# ai.net
KiCad netlist of a schematic drawn in Altium Designer
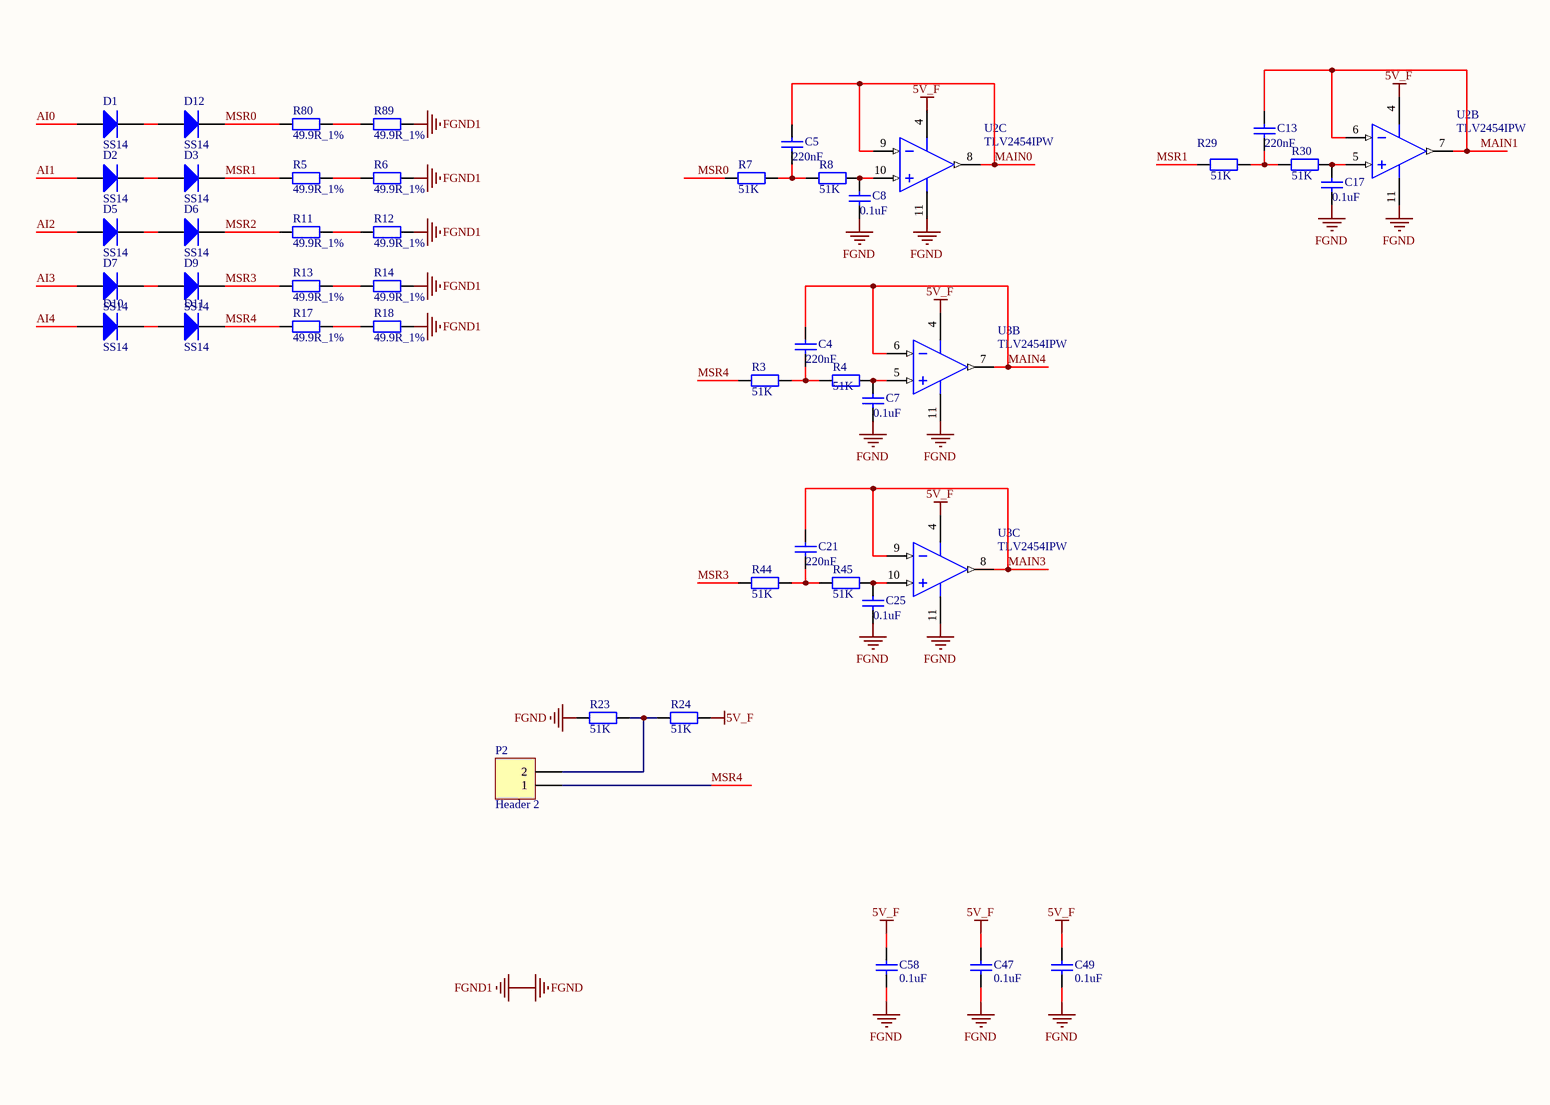
[diagram p0: ai.SchDoc, top left]
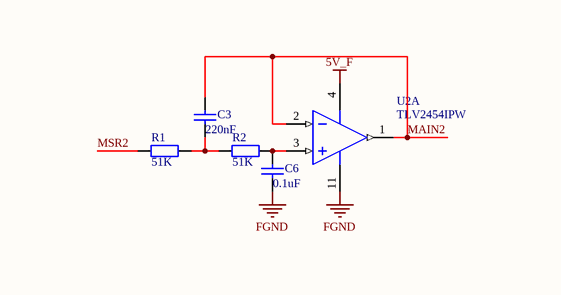
[diagram p1: ai.SchDoc, top right]
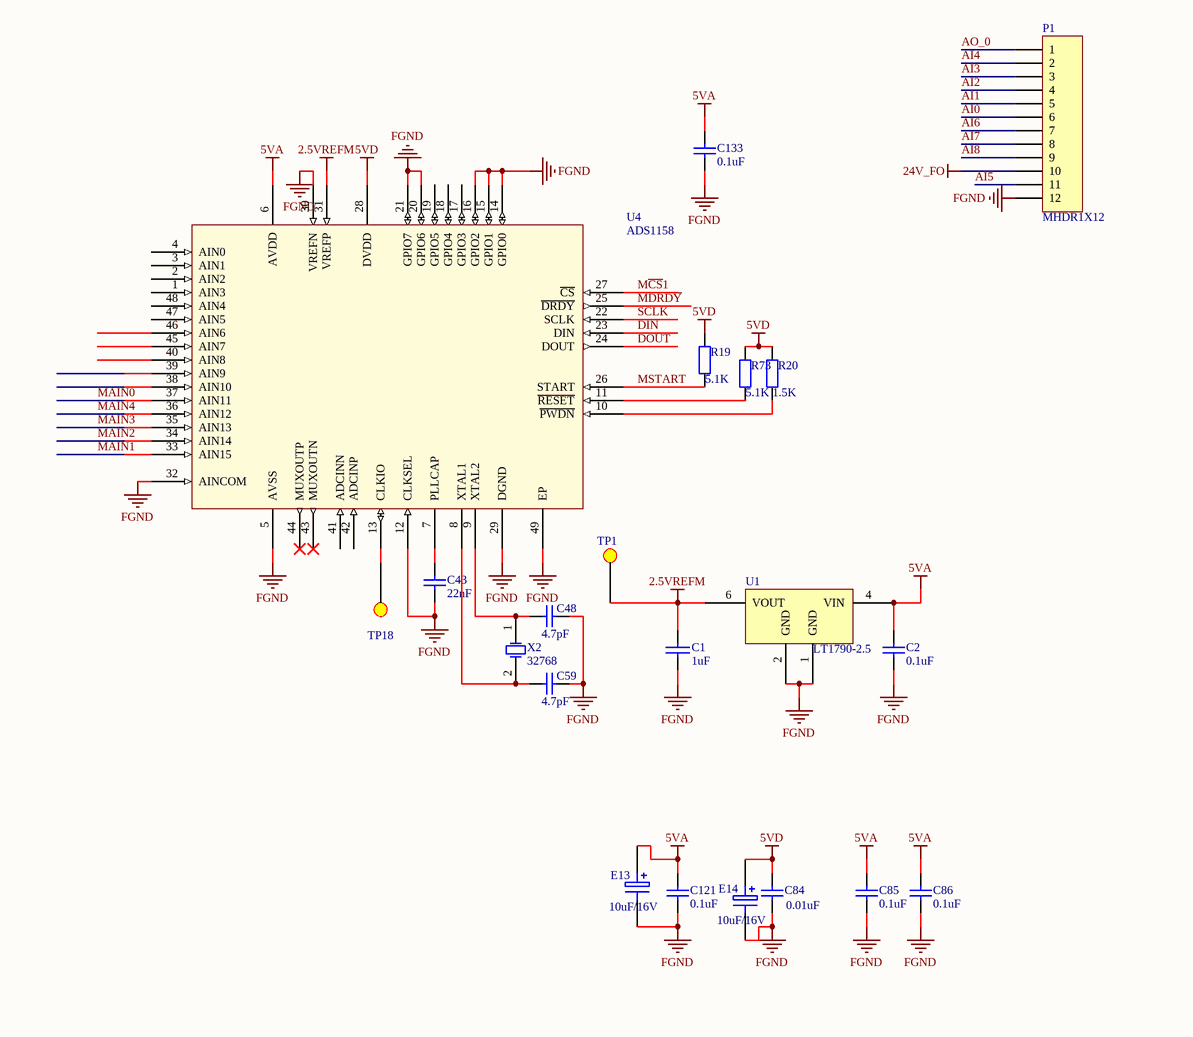
[diagram p2: ai.SchDoc, bottom left]
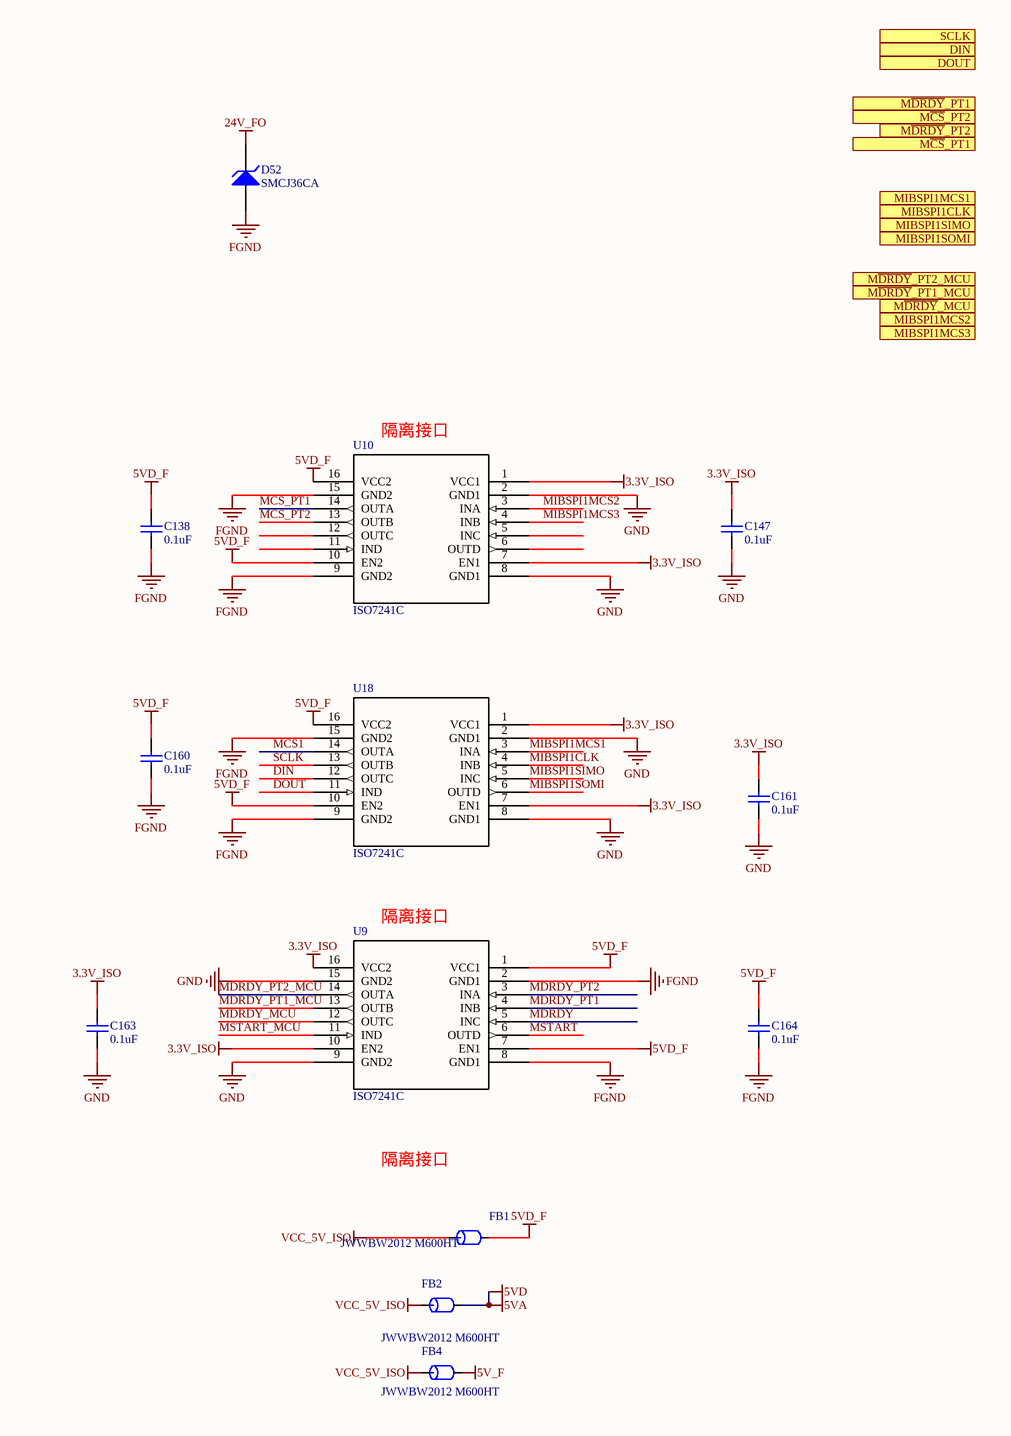
[diagram p3: ai.SchDoc, bottom right]

(export (version "E")
  (design (tool "Eeschema 10.0.6"))
  (components
    (comp (ref "C1")
      (value "1uF")
      (footprint "0603C")
      (description "Capacitor")
      (libsource (lib "*") (part "CAP"))
    )
    (comp (ref "C2")
      (value "0.1uF")
      (footprint "0603C")
      (description "Capacitor")
      (fields (field (name "PUBLISHER") "Altium Limited"))
      (libsource (lib "Miscellaneous Devices") (part "Cap"))
    )
    (comp (ref "C3")
      (value "220nF")
      (footprint "0805C")
      (description "Capacitor")
      (fields (field (name "PUBLISHER") "Altium Limited"))
      (libsource (lib "Miscellaneous Devices") (part "Cap"))
    )
    (comp (ref "C4")
      (value "220nF")
      (footprint "0805C")
      (description "Capacitor")
      (fields (field (name "PUBLISHER") "Altium Limited"))
      (libsource (lib "Miscellaneous Devices") (part "Cap"))
    )
    (comp (ref "C5")
      (value "220nF")
      (footprint "0805C")
      (description "Capacitor")
      (fields (field (name "PUBLISHER") "Altium Limited"))
      (libsource (lib "Miscellaneous Devices") (part "Cap"))
    )
    (comp (ref "C6")
      (value "0.1uF")
      (footprint "0603C")
      (description "Capacitor")
      (fields (field (name "PUBLISHER") "Altium Limited"))
      (libsource (lib "Miscellaneous Devices") (part "Cap"))
    )
    (comp (ref "C7")
      (value "0.1uF")
      (footprint "0603C")
      (description "Capacitor")
      (fields (field (name "PUBLISHER") "Altium Limited"))
      (libsource (lib "Miscellaneous Devices") (part "Cap"))
    )
    (comp (ref "C8")
      (value "0.1uF")
      (footprint "0603C")
      (description "Capacitor")
      (fields (field (name "PUBLISHER") "Altium Limited"))
      (libsource (lib "Miscellaneous Devices") (part "Cap"))
    )
    (comp (ref "C13")
      (value "220nF")
      (footprint "0805C")
      (description "Capacitor")
      (fields (field (name "PUBLISHER") "Altium Limited"))
      (libsource (lib "Miscellaneous Devices") (part "Cap"))
    )
    (comp (ref "C17")
      (value "0.1uF")
      (footprint "0603C")
      (description "Capacitor")
      (fields (field (name "PUBLISHER") "Altium Limited"))
      (libsource (lib "Miscellaneous Devices") (part "Cap"))
    )
    (comp (ref "C21")
      (value "220nF")
      (footprint "0805C")
      (description "Capacitor")
      (fields (field (name "PUBLISHER") "Altium Limited"))
      (libsource (lib "Miscellaneous Devices") (part "Cap"))
    )
    (comp (ref "C25")
      (value "0.1uF")
      (footprint "0603C")
      (description "Capacitor")
      (fields (field (name "PUBLISHER") "Altium Limited"))
      (libsource (lib "Miscellaneous Devices") (part "Cap"))
    )
    (comp (ref "C43")
      (value "22nF")
      (footprint "0805C")
      (description "Capacitor")
      (fields (field (name "PUBLISHER") "Altium Limited"))
      (libsource (lib "Miscellaneous Devices") (part "Cap"))
    )
    (comp (ref "C47")
      (value "0.1uF")
      (footprint "0603C")
      (description "Capacitor")
      (fields (field (name "PUBLISHER") "Altium Limited"))
      (libsource (lib "Miscellaneous Devices") (part "Cap"))
    )
    (comp (ref "C48")
      (value "4.7pF")
      (footprint "0603C")
      (description "Capacitor")
      (fields (field (name "PUBLISHER") "Altium Limited"))
      (libsource (lib "Miscellaneous Devices") (part "Cap"))
    )
    (comp (ref "C49")
      (value "0.1uF")
      (footprint "0603C")
      (description "Capacitor")
      (fields (field (name "PUBLISHER") "Altium Limited"))
      (libsource (lib "Miscellaneous Devices") (part "Cap"))
    )
    (comp (ref "C58")
      (value "0.1uF")
      (footprint "0603C")
      (description "Capacitor")
      (fields (field (name "PUBLISHER") "Altium Limited"))
      (libsource (lib "Miscellaneous Devices") (part "Cap"))
    )
    (comp (ref "C59")
      (value "4.7pF")
      (footprint "0603C")
      (description "Capacitor")
      (fields (field (name "PUBLISHER") "Altium Limited"))
      (libsource (lib "Miscellaneous Devices") (part "Cap"))
    )
    (comp (ref "C84")
      (value "0.01uF")
      (footprint "0603C")
      (description "Capacitor")
      (fields (field (name "PUBLISHER") "Altium Limited"))
      (libsource (lib "Miscellaneous Devices") (part "Cap"))
    )
    (comp (ref "C85")
      (value "0.1uF")
      (footprint "0603C")
      (description "Capacitor")
      (fields (field (name "PUBLISHER") "Altium Limited"))
      (libsource (lib "Miscellaneous Devices") (part "Cap"))
    )
    (comp (ref "C86")
      (value "0.1uF")
      (footprint "0603C")
      (description "Capacitor")
      (fields (field (name "PUBLISHER") "Altium Limited"))
      (libsource (lib "Miscellaneous Devices") (part "Cap"))
    )
    (comp (ref "C121")
      (value "0.1uF")
      (footprint "0603C")
      (description "Capacitor")
      (fields (field (name "PUBLISHER") "Altium Limited"))
      (libsource (lib "Miscellaneous Devices") (part "Cap"))
    )
    (comp (ref "C133")
      (value "0.1uF")
      (footprint "0603C")
      (description "Capacitor")
      (fields (field (name "PUBLISHER") "Altium Limited"))
      (libsource (lib "Miscellaneous Devices") (part "Cap"))
    )
    (comp (ref "C138")
      (value "0.1uF")
      (footprint "0603C")
      (description "Capacitor")
      (fields (field (name "PUBLISHER") "Altium Limited"))
      (libsource (lib "Miscellaneous Devices") (part "Cap"))
    )
    (comp (ref "C147")
      (value "0.1uF")
      (footprint "0603C")
      (description "Capacitor")
      (fields (field (name "PUBLISHER") "Altium Limited"))
      (libsource (lib "Miscellaneous Devices") (part "Cap"))
    )
    (comp (ref "C160")
      (value "0.1uF")
      (footprint "0603C")
      (description "Capacitor")
      (fields (field (name "PUBLISHER") "Altium Limited"))
      (libsource (lib "Miscellaneous Devices") (part "Cap"))
    )
    (comp (ref "C161")
      (value "0.1uF")
      (footprint "0603C")
      (description "Capacitor")
      (fields (field (name "PUBLISHER") "Altium Limited"))
      (libsource (lib "Miscellaneous Devices") (part "Cap"))
    )
    (comp (ref "C163")
      (value "0.1uF")
      (footprint "0603C")
      (description "Capacitor")
      (fields (field (name "PUBLISHER") "Altium Limited"))
      (libsource (lib "Miscellaneous Devices") (part "Cap"))
    )
    (comp (ref "C164")
      (value "0.1uF")
      (footprint "0603C")
      (description "Capacitor")
      (fields (field (name "PUBLISHER") "Altium Limited"))
      (libsource (lib "Miscellaneous Devices") (part "Cap"))
    )
    (comp (ref "D1")
      (value "SS14")
      (footprint "DO-214AC")
      (description "Default Diode")
      (fields (field (name "PUBLISHER") "Altium Limited"))
      (libsource (lib "Miscellaneous Devices") (part "Diode"))
    )
    (comp (ref "D2")
      (value "SS14")
      (footprint "DO-214AC")
      (description "Default Diode")
      (fields (field (name "PUBLISHER") "Altium Limited"))
      (libsource (lib "Miscellaneous Devices") (part "Diode"))
    )
    (comp (ref "D3")
      (value "SS14")
      (footprint "DO-214AC")
      (description "Default Diode")
      (fields (field (name "PUBLISHER") "Altium Limited"))
      (libsource (lib "Miscellaneous Devices") (part "Diode"))
    )
    (comp (ref "D5")
      (value "SS14")
      (footprint "DO-214AC")
      (description "Default Diode")
      (fields (field (name "PUBLISHER") "Altium Limited"))
      (libsource (lib "Miscellaneous Devices") (part "Diode"))
    )
    (comp (ref "D6")
      (value "SS14")
      (footprint "DO-214AC")
      (description "Default Diode")
      (fields (field (name "PUBLISHER") "Altium Limited"))
      (libsource (lib "Miscellaneous Devices") (part "Diode"))
    )
    (comp (ref "D7")
      (value "SS14")
      (footprint "DO-214AC")
      (description "Default Diode")
      (fields (field (name "PUBLISHER") "Altium Limited"))
      (libsource (lib "Miscellaneous Devices") (part "Diode"))
    )
    (comp (ref "D9")
      (value "SS14")
      (footprint "DO-214AC")
      (description "Default Diode")
      (fields (field (name "PUBLISHER") "Altium Limited"))
      (libsource (lib "Miscellaneous Devices") (part "Diode"))
    )
    (comp (ref "D10")
      (value "SS14")
      (footprint "DO-214AC")
      (description "Default Diode")
      (fields (field (name "PUBLISHER") "Altium Limited"))
      (libsource (lib "Miscellaneous Devices") (part "Diode"))
    )
    (comp (ref "D11")
      (value "SS14")
      (footprint "DO-214AC")
      (description "Default Diode")
      (fields (field (name "PUBLISHER") "Altium Limited"))
      (libsource (lib "Miscellaneous Devices") (part "Diode"))
    )
    (comp (ref "D12")
      (value "SS14")
      (footprint "DO-214AC")
      (description "Default Diode")
      (fields (field (name "PUBLISHER") "Altium Limited"))
      (libsource (lib "Miscellaneous Devices") (part "Diode"))
    )
    (comp (ref "D52")
      (value "SMCJ36CA")
      (footprint "SMC")
      (description "SMBJ36CA")
      (fields (field (name "PUBLISHER") "Altium Limited"))
      (libsource (lib "Miscellaneous Devices") (part "D Zener"))
    )
    (comp (ref "E13")
      (value "10uF/16V")
      (footprint "C3528")
      (description "Electrolytic Capacitor")
      (libsource (lib "*") (part "ELECTRO1"))
    )
    (comp (ref "E14")
      (value "10uF/16V")
      (footprint "C3528")
      (description "Electrolytic Capacitor")
      (libsource (lib "*") (part "ELECTRO1"))
    )
    (comp (ref "FB1")
      (value "JWWBW2012 M600HT")
      (footprint "0805R")
      (libsource (lib "Schlib_20110825") (part "FB"))
    )
    (comp (ref "FB2")
      (value "JWWBW2012 M600HT")
      (footprint "0805R")
      (libsource (lib "Schlib_20110825") (part "FB"))
    )
    (comp (ref "FB4")
      (value "JWWBW2012 M600HT")
      (footprint "0805R")
      (libsource (lib "Schlib_20110825") (part "FB"))
    )
    (comp (ref "P1")
      (value "MHDR1X12")
      (footprint "2ETYR-5.08-12P-14-100")
      (description "Header, 12-Pin")
      (fields (field (name "PUBLISHER") "Altium Limited"))
      (libsource (lib "Miscellaneous Connectors") (part "MHDR1X12"))
    )
    (comp (ref "P2")
      (value "Header 2")
      (footprint "HDR1X2")
      (description "Header, 2-Pin")
      (fields (field (name "PUBLISHER") "Altium Limited"))
      (libsource (lib "Miscellaneous Connectors") (part "Header 2"))
    )
    (comp (ref "R1") (value "51K") (footprint "0603R") (libsource (lib "MQlibrary") (part "Res0805M")))
    (comp (ref "R2") (value "51K") (footprint "0603R") (libsource (lib "MQlibrary") (part "Res0805M")))
    (comp (ref "R3") (value "51K") (footprint "0603R") (libsource (lib "MQlibrary") (part "Res0805M")))
    (comp (ref "R4") (value "51K") (footprint "0603R") (libsource (lib "MQlibrary") (part "Res0805M")))
    (comp (ref "R5") (value "49.9R_1%") (footprint "0805R") (libsource (lib "MQlibrary") (part "Res0805M")))
    (comp (ref "R6") (value "49.9R_1%") (footprint "0805R") (libsource (lib "MQlibrary") (part "Res0805M")))
    (comp (ref "R7") (value "51K") (footprint "0603R") (libsource (lib "MQlibrary") (part "Res0805M")))
    (comp (ref "R8") (value "51K") (footprint "0603R") (libsource (lib "MQlibrary") (part "Res0805M")))
    (comp (ref "R11") (value "49.9R_1%") (footprint "0805R") (libsource (lib "MQlibrary") (part "Res0805M")))
    (comp (ref "R12") (value "49.9R_1%") (footprint "0805R") (libsource (lib "MQlibrary") (part "Res0805M")))
    (comp (ref "R13") (value "49.9R_1%") (footprint "0805R") (libsource (lib "MQlibrary") (part "Res0805M")))
    (comp (ref "R14") (value "49.9R_1%") (footprint "0805R") (libsource (lib "MQlibrary") (part "Res0805M")))
    (comp (ref "R17") (value "49.9R_1%") (footprint "0805R") (libsource (lib "MQlibrary") (part "Res0805M")))
    (comp (ref "R18") (value "49.9R_1%") (footprint "0805R") (libsource (lib "MQlibrary") (part "Res0805M")))
    (comp (ref "R19") (value "5.1K") (footprint "0603R") (libsource (lib "") (part "Res0805M_2")))
    (comp (ref "R20") (value "1.5K") (footprint "0603R") (libsource (lib "") (part "Res0805M_2")))
    (comp (ref "R23") (value "51K") (footprint "0603R") (libsource (lib "") (part "Res0805M_1")))
    (comp (ref "R24") (value "51K") (footprint "0603R") (libsource (lib "") (part "Res0805M_1")))
    (comp (ref "R29") (value "51K") (footprint "0603R") (libsource (lib "MQlibrary") (part "Res0805M")))
    (comp (ref "R30") (value "51K") (footprint "0603R") (libsource (lib "MQlibrary") (part "Res0805M")))
    (comp (ref "R44") (value "51K") (footprint "0603R") (libsource (lib "MQlibrary") (part "Res0805M")))
    (comp (ref "R45") (value "51K") (footprint "0603R") (libsource (lib "MQlibrary") (part "Res0805M")))
    (comp (ref "R73") (value "5.1K") (footprint "0603R") (libsource (lib "") (part "Res0805M_2")))
    (comp (ref "R80") (value "49.9R_1%") (footprint "0805R") (libsource (lib "MQlibrary") (part "Res0805M")))
    (comp (ref "R89") (value "49.9R_1%") (footprint "0805R") (libsource (lib "MQlibrary") (part "Res0805M")))
    (comp (ref "TP1")
      (value "TEST_POINT")
      (footprint "TPD")
      (libsource (lib "基带芯片OEM板_V1P0_张猛_20120921") (part "TEST_POINT"))
    )
    (comp (ref "TP18")
      (value "TEST_POINT")
      (footprint "TPD")
      (libsource (lib "基带芯片OEM板_V1P0_张猛_20120921") (part "TEST_POINT"))
    )
    (comp (ref "U1")
      (value "LT1790-2.5")
      (footprint "SOT23-6")
      (description "2.5V Micropower SOT-23  Low Dropout Reference")
      (libsource (lib "Schlib") (part "LT1790-2.5"))
    )
    (comp (ref "U2")
      (value "TLV2454IPW")
      (footprint "TSSOP14")
      (description "Quad High-speed, Ultra Low-power, Single-Supply TTL comparator")
      (fields (field (name "PUBLISHER") "Altium Limited"))
      (libsource (lib "Maxim Analog Comparator") (part "MAX908EPD"))
    )
    (comp (ref "U3")
      (value "TLV2454IPW")
      (footprint "TSSOP14")
      (description "Quad High-speed, Ultra Low-power, Single-Supply TTL comparator")
      (fields (field (name "PUBLISHER") "Altium Limited"))
      (libsource (lib "Maxim Analog Comparator") (part "MAX908EPD"))
    )
    (comp (ref "U4")
      (value "ADS1158")
      (footprint "S-PVFQN-N48")
      (description "16-Channel, 16-Bit Analog-to-Digital Converter")
      (libsource (lib "Schlib") (part "ADS1158"))
    )
    (comp (ref "U9") (value "ISO7241C") (footprint "SOIC16") (libsource (lib "DI16") (part "ISO7241C")))
    (comp (ref "U10") (value "ISO7241C") (footprint "SOIC16") (libsource (lib "DI16") (part "ISO7241C")))
    (comp (ref "U18") (value "ISO7241C") (footprint "SOIC16") (libsource (lib "DI16") (part "ISO7241C")))
    (comp (ref "X2")
      (value "32768")
      (footprint "A")
      (description "Crystal Oscillator")
      (fields (field (name "PUBLISHER") "Altium Limited"))
      (libsource (lib "Miscellaneous Devices") (part "XTAL"))
    )
  )
  (nets
    (net (code "1") (name "/AI0") (class "Default")
      (node (ref "D1") (pin "1") (pinfunction "A_1") (pintype "passive"))
      (node (ref "P1") (pin "6") (pinfunction "6_6") (pintype "passive"))
    )
    (net (code "2") (name "/AI1") (class "Default")
      (node (ref "D2") (pin "1") (pinfunction "A_1") (pintype "passive"))
      (node (ref "P1") (pin "5") (pinfunction "5_5") (pintype "passive"))
    )
    (net (code "3") (name "/AI2") (class "Default")
      (node (ref "D5") (pin "1") (pinfunction "A_1") (pintype "passive"))
      (node (ref "P1") (pin "4") (pinfunction "4_4") (pintype "passive"))
    )
    (net (code "4") (name "/AI3") (class "Default")
      (node (ref "D7") (pin "1") (pinfunction "A_1") (pintype "passive"))
      (node (ref "P1") (pin "3") (pinfunction "3_3") (pintype "passive"))
    )
    (net (code "5") (name "/AI4") (class "Default")
      (node (ref "D10") (pin "1") (pinfunction "A_1") (pintype "passive"))
      (node (ref "P1") (pin "2") (pinfunction "2_2") (pintype "passive"))
    )
    (net (code "6") (name "/AI5") (class "Default")
      (node (ref "P1") (pin "11") (pinfunction "11_11") (pintype "passive"))
    )
    (net (code "7") (name "/AI6") (class "Default")
      (node (ref "P1") (pin "7") (pinfunction "7_7") (pintype "passive"))
    )
    (net (code "8") (name "/AI7") (class "Default")
      (node (ref "P1") (pin "8") (pinfunction "8_8") (pintype "passive"))
    )
    (net (code "9") (name "/AI8") (class "Default")
      (node (ref "P1") (pin "9") (pinfunction "9_9") (pintype "passive"))
    )
    (net (code "10") (name "/AO_0") (class "Default")
      (node (ref "P1") (pin "1") (pinfunction "1_1") (pintype "passive"))
    )
    (net (code "11") (name "/DIN") (class "Default")
      (node (ref "U18") (pin "12") (pinfunction "OUTC_12") (pintype "output"))
      (node (ref "U4") (pin "23") (pinfunction "DIN_23") (pintype "input"))
    )
    (net (code "12") (name "/DOUT") (class "Default")
      (node (ref "U18") (pin "11") (pinfunction "IND_11") (pintype "input"))
      (node (ref "U4") (pin "24") (pinfunction "DOUT_24") (pintype "output"))
    )
    (net (code "13") (name "/MAIN0") (class "Default")
      (node (ref "C5") (pin "2") (pinfunction "2_2") (pintype "passive"))
      (node (ref "U2") (pin "8") (pinfunction "OUT_8") (pintype "output"))
      (node (ref "U2") (pin "9") (pinfunction "IN-_9") (pintype "input"))
      (node (ref "U4") (pin "37") (pinfunction "AIN11_37") (pintype "input"))
    )
    (net (code "14") (name "/MAIN1") (class "Default")
      (node (ref "C13") (pin "2") (pinfunction "2_2") (pintype "passive"))
      (node (ref "U2") (pin "6") (pinfunction "IN-_6") (pintype "input"))
      (node (ref "U2") (pin "7") (pinfunction "OUT_7") (pintype "output"))
      (node (ref "U4") (pin "33") (pinfunction "AIN15_33") (pintype "input"))
    )
    (net (code "15") (name "/MAIN2") (class "Default")
      (node (ref "C3") (pin "2") (pinfunction "2_2") (pintype "passive"))
      (node (ref "U2") (pin "1") (pinfunction "OUT_1") (pintype "output"))
      (node (ref "U2") (pin "2") (pinfunction "IN-_2") (pintype "input"))
      (node (ref "U4") (pin "34") (pinfunction "AIN14_34") (pintype "input"))
    )
    (net (code "16") (name "/MAIN3") (class "Default")
      (node (ref "C21") (pin "2") (pinfunction "2_2") (pintype "passive"))
      (node (ref "U3") (pin "8") (pinfunction "OUT_8") (pintype "output"))
      (node (ref "U3") (pin "9") (pinfunction "IN-_9") (pintype "input"))
      (node (ref "U4") (pin "35") (pinfunction "AIN13_35") (pintype "input"))
    )
    (net (code "17") (name "/MAIN4") (class "Default")
      (node (ref "C4") (pin "2") (pinfunction "2_2") (pintype "passive"))
      (node (ref "U3") (pin "6") (pinfunction "IN-_6") (pintype "input"))
      (node (ref "U3") (pin "7") (pinfunction "OUT_7") (pintype "output"))
      (node (ref "U4") (pin "36") (pinfunction "AIN12_36") (pintype "input"))
    )
    (net (code "18") (name "/MIBSPI1CLK") (class "Default")
      (node (ref "U18") (pin "4") (pinfunction "INB_4") (pintype "input"))
    )
    (net (code "19") (name "/MIBSPI1MCS1") (class "Default")
      (node (ref "U18") (pin "3") (pinfunction "INA_3") (pintype "input"))
    )
    (net (code "20") (name "/MIBSPI1MCS2") (class "Default")
      (node (ref "U10") (pin "3") (pinfunction "INA_3") (pintype "input"))
    )
    (net (code "21") (name "/MIBSPI1MCS3") (class "Default")
      (node (ref "U10") (pin "4") (pinfunction "INB_4") (pintype "input"))
    )
    (net (code "22") (name "/MIBSPI1SIMO") (class "Default")
      (node (ref "U18") (pin "5") (pinfunction "INC_5") (pintype "input"))
    )
    (net (code "23") (name "/MIBSPI1SOMI") (class "Default")
      (node (ref "U18") (pin "6") (pinfunction "OUTD_6") (pintype "output"))
    )
    (net (code "24") (name "/MSR0") (class "Default")
      (node (ref "D12") (pin "2") (pinfunction "K_2") (pintype "passive"))
      (node (ref "R7") (pin "2") (pinfunction "2_2") (pintype "passive"))
      (node (ref "R80") (pin "2") (pinfunction "2_2") (pintype "passive"))
    )
    (net (code "25") (name "/MSR1") (class "Default")
      (node (ref "D3") (pin "2") (pinfunction "K_2") (pintype "passive"))
      (node (ref "R29") (pin "2") (pinfunction "2_2") (pintype "passive"))
      (node (ref "R5") (pin "2") (pinfunction "2_2") (pintype "passive"))
    )
    (net (code "26") (name "/MSR2") (class "Default")
      (node (ref "D6") (pin "2") (pinfunction "K_2") (pintype "passive"))
      (node (ref "R1") (pin "2") (pinfunction "2_2") (pintype "passive"))
      (node (ref "R11") (pin "2") (pinfunction "2_2") (pintype "passive"))
    )
    (net (code "27") (name "/MSR3") (class "Default")
      (node (ref "D9") (pin "2") (pinfunction "K_2") (pintype "passive"))
      (node (ref "R13") (pin "2") (pinfunction "2_2") (pintype "passive"))
      (node (ref "R44") (pin "2") (pinfunction "2_2") (pintype "passive"))
    )
    (net (code "28") (name "/MSR4") (class "Default")
      (node (ref "D11") (pin "2") (pinfunction "K_2") (pintype "passive"))
      (node (ref "P2") (pin "1") (pinfunction "1_1") (pintype "passive"))
      (node (ref "R17") (pin "2") (pinfunction "2_2") (pintype "passive"))
      (node (ref "R3") (pin "2") (pinfunction "2_2") (pintype "passive"))
    )
    (net (code "29") (name "/MSTART") (class "Default")
      (node (ref "R19") (pin "2") (pinfunction "2_2") (pintype "passive"))
      (node (ref "U4") (pin "26") (pinfunction "START_26") (pintype "input"))
      (node (ref "U9") (pin "6") (pinfunction "OUTD_6") (pintype "output"))
    )
    (net (code "30") (name "/MSTART_MCU") (class "Default")
      (node (ref "U9") (pin "11") (pinfunction "IND_11") (pintype "input"))
    )
    (net (code "31") (name "/M~{CS}1") (class "Default")
      (node (ref "U18") (pin "14") (pinfunction "OUTA_14") (pintype "output"))
      (node (ref "U4") (pin "27") (pinfunction "~{CS}_27") (pintype "input"))
    )
    (net (code "32") (name "/M~{CS}_PT1") (class "Default")
      (node (ref "U10") (pin "14") (pinfunction "OUTA_14") (pintype "output"))
    )
    (net (code "33") (name "/M~{CS}_PT2") (class "Default")
      (node (ref "U10") (pin "13") (pinfunction "OUTB_13") (pintype "output"))
    )
    (net (code "34") (name "/M~{DRDY}") (class "Default")
      (node (ref "U4") (pin "25") (pinfunction "~{DRDY}_25") (pintype "output"))
      (node (ref "U9") (pin "5") (pinfunction "INC_5") (pintype "input"))
    )
    (net (code "35") (name "/M~{DRDY}_MCU") (class "Default")
      (node (ref "U9") (pin "12") (pinfunction "OUTC_12") (pintype "output"))
    )
    (net (code "36") (name "/M~{DRDY}_PT1") (class "Default")
      (node (ref "U9") (pin "4") (pinfunction "INB_4") (pintype "input"))
    )
    (net (code "37") (name "/M~{DRDY}_PT1_MCU") (class "Default")
      (node (ref "U9") (pin "13") (pinfunction "OUTB_13") (pintype "output"))
    )
    (net (code "38") (name "/M~{DRDY}_PT2") (class "Default")
      (node (ref "U9") (pin "3") (pinfunction "INA_3") (pintype "input"))
    )
    (net (code "39") (name "/M~{DRDY}_PT2_MCU") (class "Default")
      (node (ref "U9") (pin "14") (pinfunction "OUTA_14") (pintype "output"))
    )
    (net (code "40") (name "/SCLK") (class "Default")
      (node (ref "U18") (pin "13") (pinfunction "OUTB_13") (pintype "output"))
      (node (ref "U4") (pin "22") (pinfunction "SCLK_22") (pintype "input"))
    )
    (net (code "41") (name "2.5VREFM") (class "Default")
      (node (ref "C1") (pin "1") (pinfunction "1_1") (pintype "passive"))
      (node (ref "TP1") (pin "1") (pinfunction "1_1") (pintype "passive"))
      (node (ref "U1") (pin "6") (pinfunction "VOUT_6") (pintype "power_in"))
      (node (ref "U4") (pin "31") (pinfunction "VREFP_31") (pintype "input"))
    )
    (net (code "42") (name "3.3V_ISO") (class "Default")
      (node (ref "C147") (pin "2") (pinfunction "2_2") (pintype "passive"))
      (node (ref "C161") (pin "2") (pinfunction "2_2") (pintype "passive"))
      (node (ref "C163") (pin "2") (pinfunction "2_2") (pintype "passive"))
      (node (ref "U10") (pin "1") (pinfunction "VCC1_1") (pintype "power_in"))
      (node (ref "U10") (pin "7") (pinfunction "EN1_7") (pintype "passive"))
      (node (ref "U18") (pin "1") (pinfunction "VCC1_1") (pintype "power_in"))
      (node (ref "U18") (pin "7") (pinfunction "EN1_7") (pintype "passive"))
      (node (ref "U9") (pin "10") (pinfunction "EN2_10") (pintype "passive"))
      (node (ref "U9") (pin "16") (pinfunction "VCC2_16") (pintype "power_in"))
    )
    (net (code "43") (name "5VA") (class "Default")
      (node (ref "C121") (pin "2") (pinfunction "2_2") (pintype "passive"))
      (node (ref "C133") (pin "2") (pinfunction "2_2") (pintype "passive"))
      (node (ref "C2") (pin "2") (pinfunction "2_2") (pintype "passive"))
      (node (ref "C84") (pin "2") (pinfunction "2_2") (pintype "passive"))
      (node (ref "C85") (pin "2") (pinfunction "2_2") (pintype "passive"))
      (node (ref "C86") (pin "2") (pinfunction "2_2") (pintype "passive"))
      (node (ref "E13") (pin "1") (pinfunction "1_1") (pintype "passive"))
      (node (ref "E14") (pin "1") (pinfunction "1_1") (pintype "passive"))
      (node (ref "FB2") (pin "2") (pintype "passive"))
      (node (ref "R19") (pin "1") (pinfunction "1_1") (pintype "passive"))
      (node (ref "R20") (pin "1") (pinfunction "1_1") (pintype "passive"))
      (node (ref "R73") (pin "1") (pinfunction "1_1") (pintype "passive"))
      (node (ref "U1") (pin "4") (pinfunction "VIN_4") (pintype "power_in"))
      (node (ref "U4") (pin "28") (pinfunction "DVDD_28") (pintype "power_in"))
      (node (ref "U4") (pin "6") (pinfunction "AVDD_6") (pintype "passive"))
    )
    (net (code "44") (name "5VD_F") (class "Default")
      (node (ref "C138") (pin "2") (pinfunction "2_2") (pintype "passive"))
      (node (ref "C160") (pin "2") (pinfunction "2_2") (pintype "passive"))
      (node (ref "C164") (pin "2") (pinfunction "2_2") (pintype "passive"))
      (node (ref "FB1") (pin "2") (pintype "passive"))
      (node (ref "U10") (pin "10") (pinfunction "EN2_10") (pintype "passive"))
      (node (ref "U10") (pin "16") (pinfunction "VCC2_16") (pintype "power_in"))
      (node (ref "U18") (pin "10") (pinfunction "EN2_10") (pintype "passive"))
      (node (ref "U18") (pin "16") (pinfunction "VCC2_16") (pintype "power_in"))
      (node (ref "U9") (pin "1") (pinfunction "VCC1_1") (pintype "power_in"))
      (node (ref "U9") (pin "7") (pinfunction "EN1_7") (pintype "passive"))
    )
    (net (code "45") (name "5V_F") (class "Default")
      (node (ref "C47") (pin "2") (pinfunction "2_2") (pintype "passive"))
      (node (ref "C49") (pin "2") (pinfunction "2_2") (pintype "passive"))
      (node (ref "C58") (pin "2") (pinfunction "2_2") (pintype "passive"))
      (node (ref "FB4") (pin "2") (pintype "passive"))
      (node (ref "R24") (pin "2") (pinfunction "2_2") (pintype "passive"))
      (node (ref "U2") (pin "4") (pinfunction "V+_4") (pintype "power_in"))
      (node (ref "U3") (pin "4") (pinfunction "V+_4") (pintype "power_in"))
    )
    (net (code "46") (name "24V_FO") (class "Default")
      (node (ref "D52") (pin "2") (pinfunction "K_2") (pintype "passive"))
      (node (ref "P1") (pin "10") (pinfunction "10_10") (pintype "passive"))
    )
    (net (code "47") (name "FGND") (class "Default")
      (node (ref "C1") (pin "2") (pinfunction "2_2") (pintype "passive"))
      (node (ref "C121") (pin "1") (pinfunction "1_1") (pintype "passive"))
      (node (ref "C133") (pin "1") (pinfunction "1_1") (pintype "passive"))
      (node (ref "C138") (pin "1") (pinfunction "1_1") (pintype "passive"))
      (node (ref "C160") (pin "1") (pinfunction "1_1") (pintype "passive"))
      (node (ref "C164") (pin "1") (pinfunction "1_1") (pintype "passive"))
      (node (ref "C17") (pin "1") (pinfunction "1_1") (pintype "passive"))
      (node (ref "C2") (pin "1") (pinfunction "1_1") (pintype "passive"))
      (node (ref "C25") (pin "1") (pinfunction "1_1") (pintype "passive"))
      (node (ref "C43") (pin "2") (pinfunction "2_2") (pintype "passive"))
      (node (ref "C47") (pin "1") (pinfunction "1_1") (pintype "passive"))
      (node (ref "C48") (pin "2") (pinfunction "2_2") (pintype "passive"))
      (node (ref "C49") (pin "1") (pinfunction "1_1") (pintype "passive"))
      (node (ref "C58") (pin "1") (pinfunction "1_1") (pintype "passive"))
      (node (ref "C59") (pin "2") (pinfunction "2_2") (pintype "passive"))
      (node (ref "C6") (pin "1") (pinfunction "1_1") (pintype "passive"))
      (node (ref "C7") (pin "1") (pinfunction "1_1") (pintype "passive"))
      (node (ref "C8") (pin "1") (pinfunction "1_1") (pintype "passive"))
      (node (ref "C84") (pin "1") (pinfunction "1_1") (pintype "passive"))
      (node (ref "C85") (pin "1") (pinfunction "1_1") (pintype "passive"))
      (node (ref "C86") (pin "1") (pinfunction "1_1") (pintype "passive"))
      (node (ref "D52") (pin "1") (pinfunction "A_1") (pintype "passive"))
      (node (ref "E13") (pin "2") (pinfunction "2_2") (pintype "passive"))
      (node (ref "E14") (pin "2") (pinfunction "2_2") (pintype "passive"))
      (node (ref "P1") (pin "12") (pinfunction "12_12") (pintype "passive"))
      (node (ref "R12") (pin "1") (pinfunction "1_1") (pintype "passive"))
      (node (ref "R14") (pin "1") (pinfunction "1_1") (pintype "passive"))
      (node (ref "R18") (pin "1") (pinfunction "1_1") (pintype "passive"))
      (node (ref "R23") (pin "1") (pinfunction "1_1") (pintype "passive"))
      (node (ref "R6") (pin "1") (pinfunction "1_1") (pintype "passive"))
      (node (ref "R89") (pin "1") (pinfunction "1_1") (pintype "passive"))
      (node (ref "U1") (pin "1") (pinfunction "GND_1") (pintype "power_in"))
      (node (ref "U1") (pin "2") (pinfunction "GND_2") (pintype "power_in"))
      (node (ref "U10") (pin "15") (pinfunction "GND2_15") (pintype "power_in"))
      (node (ref "U10") (pin "9") (pinfunction "GND2_9") (pintype "power_in"))
      (node (ref "U18") (pin "15") (pinfunction "GND2_15") (pintype "power_in"))
      (node (ref "U18") (pin "9") (pinfunction "GND2_9") (pintype "power_in"))
      (node (ref "U2") (pin "11") (pinfunction "GND_11") (pintype "power_in"))
      (node (ref "U3") (pin "11") (pinfunction "GND_11") (pintype "power_in"))
      (node (ref "U4") (pin "12") (pinfunction "CLKSEL_12") (pintype "input"))
      (node (ref "U4") (pin "14") (pinfunction "GPIO0_14") (pintype "bidirectional"))
      (node (ref "U4") (pin "15") (pinfunction "GPIO1_15") (pintype "bidirectional"))
      (node (ref "U4") (pin "16") (pinfunction "GPIO2_16") (pintype "bidirectional"))
      (node (ref "U4") (pin "20") (pinfunction "GPIO6_20") (pintype "bidirectional"))
      (node (ref "U4") (pin "21") (pinfunction "GPIO7_21") (pintype "bidirectional"))
      (node (ref "U4") (pin "29") (pinfunction "DGND_29") (pintype "power_in"))
      (node (ref "U4") (pin "30") (pinfunction "VREFN_30") (pintype "input"))
      (node (ref "U4") (pin "32") (pinfunction "AINCOM_32") (pintype "input"))
      (node (ref "U4") (pin "49") (pinfunction "EP_49") (pintype "passive"))
      (node (ref "U4") (pin "5") (pinfunction "AVSS_5") (pintype "power_in"))
      (node (ref "U9") (pin "2") (pinfunction "GND1_2") (pintype "power_in"))
      (node (ref "U9") (pin "8") (pinfunction "GND1_8") (pintype "power_in"))
    )
    (net (code "48") (name "GND") (class "Default")
      (node (ref "C147") (pin "1") (pinfunction "1_1") (pintype "passive"))
      (node (ref "C161") (pin "1") (pinfunction "1_1") (pintype "passive"))
      (node (ref "C163") (pin "1") (pinfunction "1_1") (pintype "passive"))
      (node (ref "U10") (pin "2") (pinfunction "GND1_2") (pintype "power_in"))
      (node (ref "U10") (pin "8") (pinfunction "GND1_8") (pintype "power_in"))
      (node (ref "U18") (pin "2") (pinfunction "GND1_2") (pintype "power_in"))
      (node (ref "U18") (pin "8") (pinfunction "GND1_8") (pintype "power_in"))
      (node (ref "U9") (pin "15") (pinfunction "GND2_15") (pintype "power_in"))
      (node (ref "U9") (pin "9") (pinfunction "GND2_9") (pintype "power_in"))
    )
    (net (code "49") (name "Net-(C3-Pad1)") (class "Default")
      (node (ref "C3") (pin "1") (pinfunction "1_1") (pintype "passive"))
      (node (ref "R1") (pin "1") (pinfunction "1_1") (pintype "passive"))
      (node (ref "R2") (pin "2") (pinfunction "2_2") (pintype "passive"))
    )
    (net (code "50") (name "Net-(C4-Pad1)") (class "Default")
      (node (ref "C4") (pin "1") (pinfunction "1_1") (pintype "passive"))
      (node (ref "R3") (pin "1") (pinfunction "1_1") (pintype "passive"))
      (node (ref "R4") (pin "2") (pinfunction "2_2") (pintype "passive"))
    )
    (net (code "51") (name "Net-(C5-Pad1)") (class "Default")
      (node (ref "C5") (pin "1") (pinfunction "1_1") (pintype "passive"))
      (node (ref "R7") (pin "1") (pinfunction "1_1") (pintype "passive"))
      (node (ref "R8") (pin "2") (pinfunction "2_2") (pintype "passive"))
    )
    (net (code "52") (name "Net-(C13-Pad1)") (class "Default")
      (node (ref "C13") (pin "1") (pinfunction "1_1") (pintype "passive"))
      (node (ref "R29") (pin "1") (pinfunction "1_1") (pintype "passive"))
      (node (ref "R30") (pin "2") (pinfunction "2_2") (pintype "passive"))
    )
    (net (code "53") (name "Net-(C21-Pad1)") (class "Default")
      (node (ref "C21") (pin "1") (pinfunction "1_1") (pintype "passive"))
      (node (ref "R44") (pin "1") (pinfunction "1_1") (pintype "passive"))
      (node (ref "R45") (pin "2") (pinfunction "2_2") (pintype "passive"))
    )
    (net (code "54") (name "Net-(D1-K)") (class "Default")
      (node (ref "D1") (pin "2") (pinfunction "K_2") (pintype "passive"))
      (node (ref "D12") (pin "1") (pinfunction "A_1") (pintype "passive"))
    )
    (net (code "55") (name "Net-(D2-K)") (class "Default")
      (node (ref "D2") (pin "2") (pinfunction "K_2") (pintype "passive"))
      (node (ref "D3") (pin "1") (pinfunction "A_1") (pintype "passive"))
    )
    (net (code "56") (name "Net-(D5-K)") (class "Default")
      (node (ref "D5") (pin "2") (pinfunction "K_2") (pintype "passive"))
      (node (ref "D6") (pin "1") (pinfunction "A_1") (pintype "passive"))
    )
    (net (code "57") (name "Net-(D7-K)") (class "Default")
      (node (ref "D7") (pin "2") (pinfunction "K_2") (pintype "passive"))
      (node (ref "D9") (pin "1") (pinfunction "A_1") (pintype "passive"))
    )
    (net (code "58") (name "Net-(D10-K)") (class "Default")
      (node (ref "D10") (pin "2") (pinfunction "K_2") (pintype "passive"))
      (node (ref "D11") (pin "1") (pinfunction "A_1") (pintype "passive"))
    )
    (net (code "59") (name "Net-(P2-Pad2)") (class "Default")
      (node (ref "P2") (pin "2") (pinfunction "2_2") (pintype "passive"))
      (node (ref "R23") (pin "2") (pinfunction "2_2") (pintype "passive"))
      (node (ref "R24") (pin "1") (pinfunction "1_1") (pintype "passive"))
    )
    (net (code "60") (name "Net-(R5-Pad1)") (class "Default")
      (node (ref "R5") (pin "1") (pinfunction "1_1") (pintype "passive"))
      (node (ref "R6") (pin "2") (pinfunction "2_2") (pintype "passive"))
    )
    (net (code "61") (name "Net-(R11-Pad1)") (class "Default")
      (node (ref "R11") (pin "1") (pinfunction "1_1") (pintype "passive"))
      (node (ref "R12") (pin "2") (pinfunction "2_2") (pintype "passive"))
    )
    (net (code "62") (name "Net-(R13-Pad1)") (class "Default")
      (node (ref "R13") (pin "1") (pinfunction "1_1") (pintype "passive"))
      (node (ref "R14") (pin "2") (pinfunction "2_2") (pintype "passive"))
    )
    (net (code "63") (name "Net-(R17-Pad1)") (class "Default")
      (node (ref "R17") (pin "1") (pinfunction "1_1") (pintype "passive"))
      (node (ref "R18") (pin "2") (pinfunction "2_2") (pintype "passive"))
    )
    (net (code "64") (name "Net-(R80-Pad1)") (class "Default")
      (node (ref "R80") (pin "1") (pinfunction "1_1") (pintype "passive"))
      (node (ref "R89") (pin "2") (pinfunction "2_2") (pintype "passive"))
    )
    (net (code "65") (name "Net-(U2A-IN+)") (class "Default")
      (node (ref "C6") (pin "2") (pinfunction "2_2") (pintype "passive"))
      (node (ref "R2") (pin "1") (pinfunction "1_1") (pintype "passive"))
      (node (ref "U2") (pin "3") (pinfunction "IN+_3") (pintype "input"))
    )
    (net (code "66") (name "Net-(U2B-IN+)") (class "Default")
      (node (ref "C17") (pin "2") (pinfunction "2_2") (pintype "passive"))
      (node (ref "R30") (pin "1") (pinfunction "1_1") (pintype "passive"))
      (node (ref "U2") (pin "5") (pinfunction "IN+_5") (pintype "input"))
    )
    (net (code "67") (name "Net-(U2C-IN+)") (class "Default")
      (node (ref "C8") (pin "2") (pinfunction "2_2") (pintype "passive"))
      (node (ref "R8") (pin "1") (pinfunction "1_1") (pintype "passive"))
      (node (ref "U2") (pin "10") (pinfunction "IN+_10") (pintype "input"))
    )
    (net (code "68") (name "Net-(U3B-IN+)") (class "Default")
      (node (ref "C7") (pin "2") (pinfunction "2_2") (pintype "passive"))
      (node (ref "R4") (pin "1") (pinfunction "1_1") (pintype "passive"))
      (node (ref "U3") (pin "5") (pinfunction "IN+_5") (pintype "input"))
    )
    (net (code "69") (name "Net-(U3C-IN+)") (class "Default")
      (node (ref "C25") (pin "2") (pinfunction "2_2") (pintype "passive"))
      (node (ref "R45") (pin "1") (pinfunction "1_1") (pintype "passive"))
      (node (ref "U3") (pin "10") (pinfunction "IN+_10") (pintype "input"))
    )
    (net (code "70") (name "Net-(U4-CLKIO)") (class "Default")
      (node (ref "TP18") (pin "1") (pinfunction "1_1") (pintype "passive"))
      (node (ref "U4") (pin "13") (pinfunction "CLKIO_13") (pintype "bidirectional"))
    )
    (net (code "71") (name "Net-(U4-PLLCAP)") (class "Default")
      (node (ref "C43") (pin "1") (pinfunction "1_1") (pintype "passive"))
      (node (ref "U4") (pin "7") (pinfunction "PLLCAP_7") (pintype "power_in"))
    )
    (net (code "72") (name "Net-(U4-XTAL1)") (class "Default")
      (node (ref "C59") (pin "1") (pinfunction "1_1") (pintype "passive"))
      (node (ref "U4") (pin "8") (pinfunction "XTAL1_8") (pintype "passive"))
      (node (ref "X2") (pin "2") (pinfunction "OSC2_2") (pintype "passive"))
    )
    (net (code "73") (name "Net-(U4-XTAL2)") (class "Default")
      (node (ref "C48") (pin "1") (pinfunction "1_1") (pintype "passive"))
      (node (ref "U4") (pin "9") (pinfunction "XTAL2_9") (pintype "passive"))
      (node (ref "X2") (pin "1") (pinfunction "OSC1_1") (pintype "passive"))
    )
    (net (code "74") (name "Net-(U4-~{PWDN})") (class "Default")
      (node (ref "R20") (pin "2") (pinfunction "2_2") (pintype "passive"))
      (node (ref "U4") (pin "10") (pinfunction "~{PWDN}_10") (pintype "input"))
    )
    (net (code "75") (name "Net-(U4-~{RESET})") (class "Default")
      (node (ref "R73") (pin "2") (pinfunction "2_2") (pintype "passive"))
      (node (ref "U4") (pin "11") (pinfunction "~{RESET}_11") (pintype "input"))
    )
    (net (code "76") (name "VCC_5V_ISO") (class "Default")
      (node (ref "FB1") (pin "1") (pintype "passive"))
      (node (ref "FB2") (pin "1") (pintype "passive"))
      (node (ref "FB4") (pin "1") (pintype "passive"))
    )
    (net (code "77") (name "unconnected-(U1-DNC-Pad3)") (class "Default")
      (node (ref "U1") (pin "3") (pinfunction "DNC_3") (pintype "passive"))
    )
    (net (code "78") (name "unconnected-(U1-DNC-Pad5)") (class "Default")
      (node (ref "U1") (pin "5") (pinfunction "DNC_5") (pintype "passive"))
    )
    (net (code "79") (name "unconnected-(U4-ADCINN-Pad41)") (class "Default")
      (node (ref "U4") (pin "41") (pinfunction "ADCINN_41") (pintype "input"))
    )
    (net (code "80") (name "unconnected-(U4-ADCINP-Pad42)") (class "Default")
      (node (ref "U4") (pin "42") (pinfunction "ADCINP_42") (pintype "input"))
    )
    (net (code "81") (name "unconnected-(U4-AIN0-Pad4)") (class "Default")
      (node (ref "U4") (pin "4") (pinfunction "AIN0_4") (pintype "input"))
    )
    (net (code "82") (name "unconnected-(U4-AIN1-Pad3)") (class "Default")
      (node (ref "U4") (pin "3") (pinfunction "AIN1_3") (pintype "input"))
    )
    (net (code "83") (name "unconnected-(U4-AIN2-Pad2)") (class "Default")
      (node (ref "U4") (pin "2") (pinfunction "AIN2_2") (pintype "input"))
    )
    (net (code "84") (name "unconnected-(U4-AIN3-Pad1)") (class "Default")
      (node (ref "U4") (pin "1") (pinfunction "AIN3_1") (pintype "input"))
    )
    (net (code "85") (name "unconnected-(U4-AIN4-Pad48)") (class "Default")
      (node (ref "U4") (pin "48") (pinfunction "AIN4_48") (pintype "input"))
    )
    (net (code "86") (name "unconnected-(U4-AIN5-Pad47)") (class "Default")
      (node (ref "U4") (pin "47") (pinfunction "AIN5_47") (pintype "input"))
    )
    (net (code "87") (name "unconnected-(U4-AIN6-Pad46)") (class "Default")
      (node (ref "U4") (pin "46") (pinfunction "AIN6_46") (pintype "input"))
    )
    (net (code "88") (name "unconnected-(U4-AIN7-Pad45)") (class "Default")
      (node (ref "U4") (pin "45") (pinfunction "AIN7_45") (pintype "input"))
    )
    (net (code "89") (name "unconnected-(U4-AIN8-Pad40)") (class "Default")
      (node (ref "U4") (pin "40") (pinfunction "AIN8_40") (pintype "input"))
    )
    (net (code "90") (name "unconnected-(U4-AIN9-Pad39)") (class "Default")
      (node (ref "U4") (pin "39") (pinfunction "AIN9_39") (pintype "input"))
    )
    (net (code "91") (name "unconnected-(U4-AIN10-Pad38)") (class "Default")
      (node (ref "U4") (pin "38") (pinfunction "AIN10_38") (pintype "input"))
    )
    (net (code "92") (name "unconnected-(U4-GPIO3-Pad17)") (class "Default")
      (node (ref "U4") (pin "17") (pinfunction "GPIO3_17") (pintype "bidirectional"))
    )
    (net (code "93") (name "unconnected-(U4-GPIO4-Pad18)") (class "Default")
      (node (ref "U4") (pin "18") (pinfunction "GPIO4_18") (pintype "bidirectional"))
    )
    (net (code "94") (name "unconnected-(U4-GPIO5-Pad19)") (class "Default")
      (node (ref "U4") (pin "19") (pinfunction "GPIO5_19") (pintype "bidirectional"))
    )
    (net (code "95") (name "unconnected-(U4-MUXOUTN-Pad43)") (class "Default")
      (node (ref "U4") (pin "43") (pinfunction "MUXOUTN_43") (pintype "output+no_connect"))
    )
    (net (code "96") (name "unconnected-(U4-MUXOUTP-Pad44)") (class "Default")
      (node (ref "U4") (pin "44") (pinfunction "MUXOUTP_44") (pintype "output+no_connect"))
    )
    (net (code "97") (name "unconnected-(U10-INC-Pad5)") (class "Default")
      (node (ref "U10") (pin "5") (pinfunction "INC_5") (pintype "input"))
    )
    (net (code "98") (name "unconnected-(U10-IND-Pad11)") (class "Default")
      (node (ref "U10") (pin "11") (pinfunction "IND_11") (pintype "input"))
    )
    (net (code "99") (name "unconnected-(U10-OUTC-Pad12)") (class "Default")
      (node (ref "U10") (pin "12") (pinfunction "OUTC_12") (pintype "output"))
    )
    (net (code "100") (name "unconnected-(U10-OUTD-Pad6)") (class "Default")
      (node (ref "U10") (pin "6") (pinfunction "OUTD_6") (pintype "output"))
    )
  )
)
